# EMG_connectors_and_filters_CH_1_4.net
KiCad netlist of a schematic drawn in Altium Designer
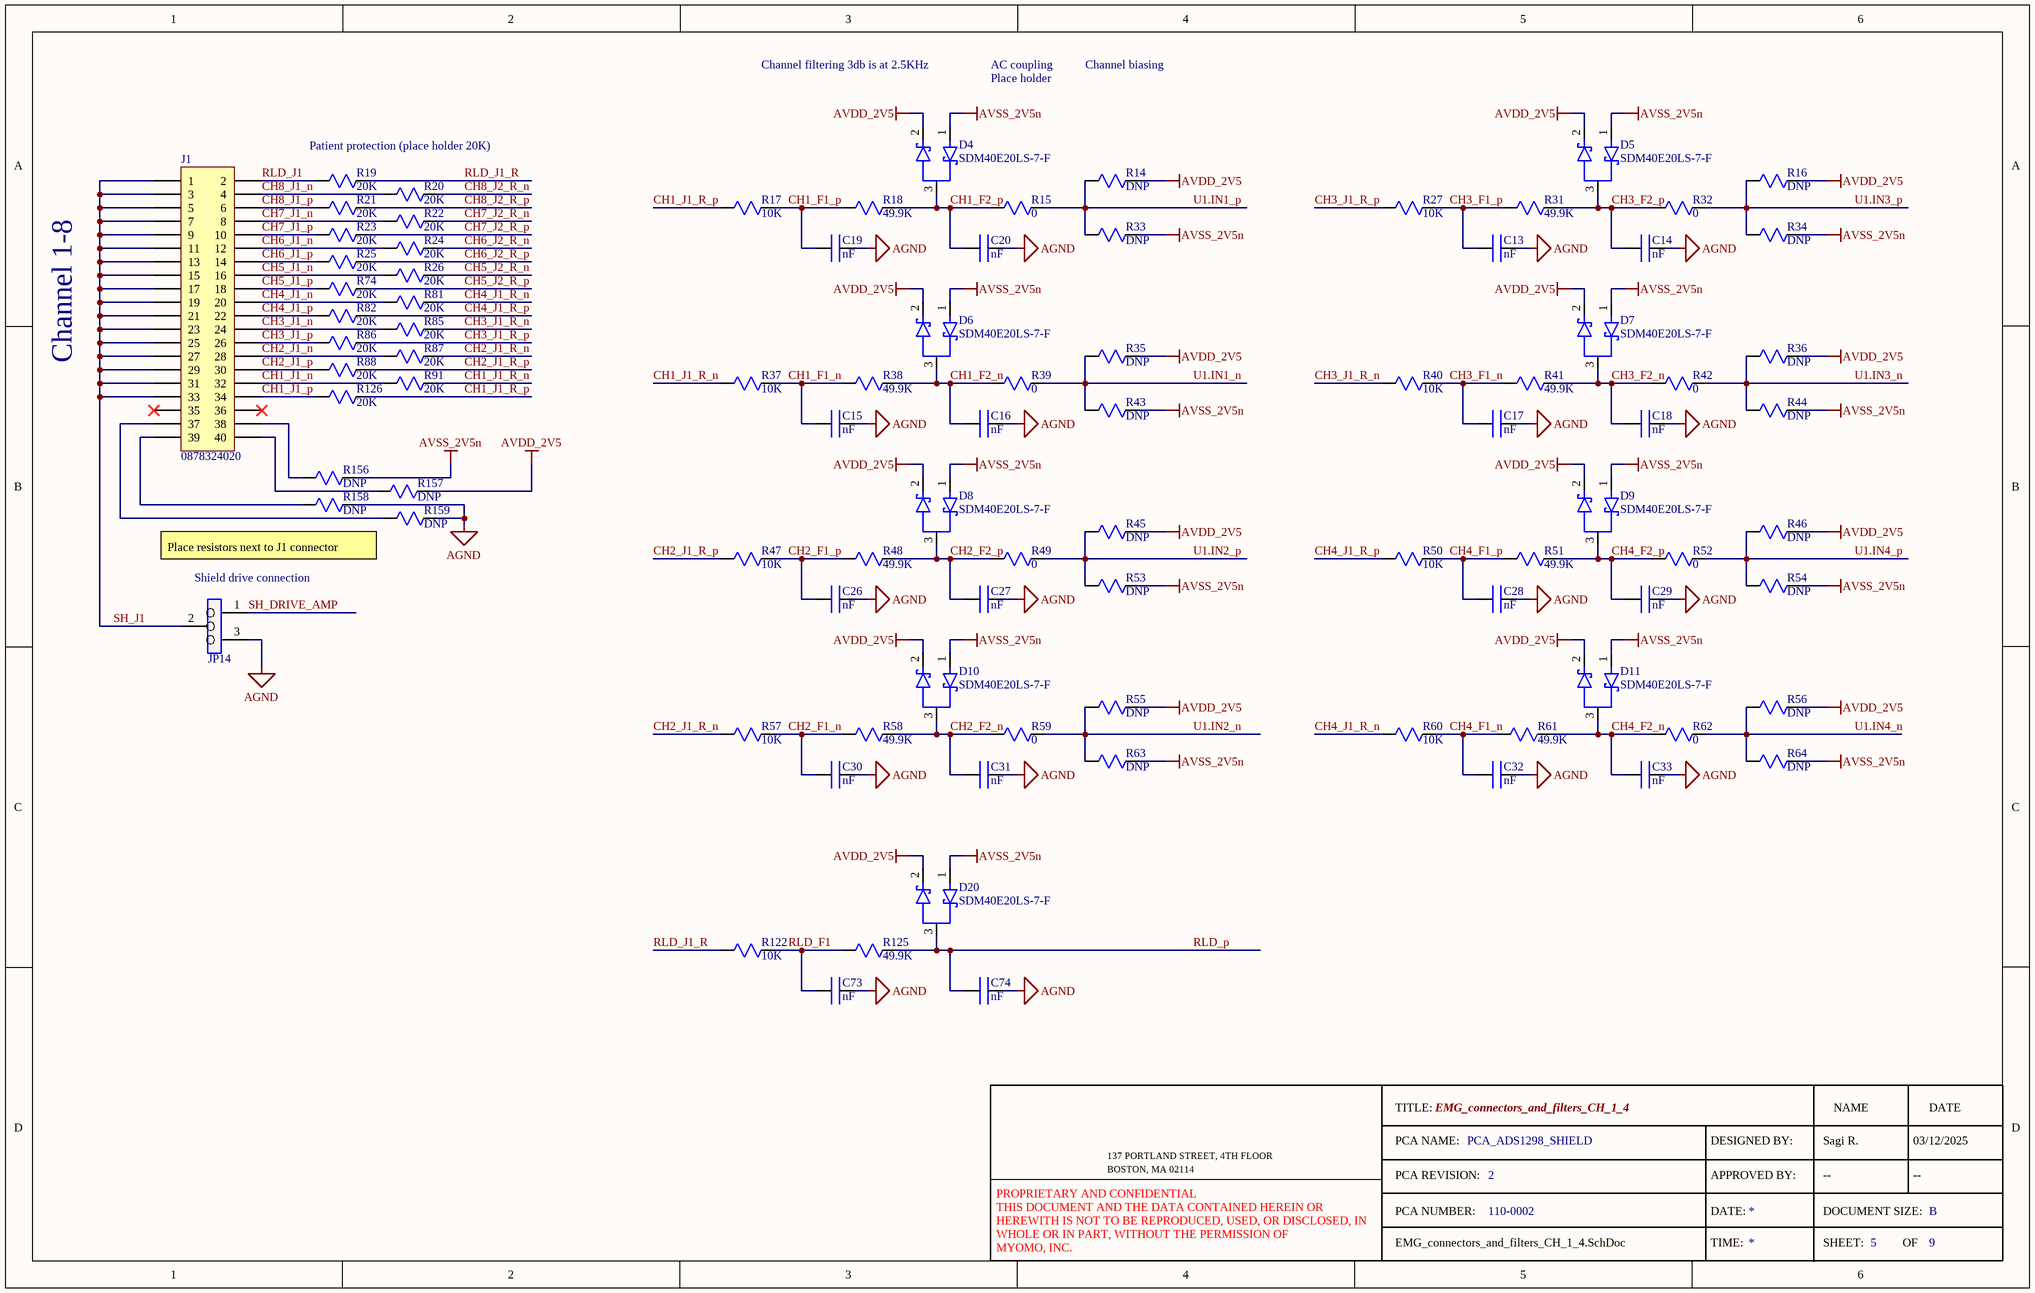
[diagram p0: EMG_connectors_and_filters_CH_1_4.SchDoc]

(export (version "E")
  (design (tool "Eeschema 10.0.6"))
  (components
    (comp (ref "C13")
      (value "nF")
      (footprint "0402")
      (description "CAP CER 1000PF 50V X7R 0402")
      (fields (field (name "MFG") "Samsung"))
      (libsource (lib "Myomo_SCH_Library") (part "C_0402_CER_1nF_50V_X7R"))
    )
    (comp (ref "C14")
      (value "nF")
      (footprint "0402")
      (description "CAP CER 1000PF 50V X7R 0402")
      (fields (field (name "MFG") "Samsung"))
      (libsource (lib "Myomo_SCH_Library") (part "C_0402_CER_1nF_50V_X7R"))
    )
    (comp (ref "C15")
      (value "nF")
      (footprint "0402")
      (description "CAP CER 1000PF 50V X7R 0402")
      (fields (field (name "MFG") "Samsung"))
      (libsource (lib "Myomo_SCH_Library") (part "C_0402_CER_1nF_50V_X7R"))
    )
    (comp (ref "C16")
      (value "nF")
      (footprint "0402")
      (description "CAP CER 1000PF 50V X7R 0402")
      (fields (field (name "MFG") "Samsung"))
      (libsource (lib "Myomo_SCH_Library") (part "C_0402_CER_1nF_50V_X7R"))
    )
    (comp (ref "C17")
      (value "nF")
      (footprint "0402")
      (description "CAP CER 1000PF 50V X7R 0402")
      (fields (field (name "MFG") "Samsung"))
      (libsource (lib "Myomo_SCH_Library") (part "C_0402_CER_1nF_50V_X7R"))
    )
    (comp (ref "C18")
      (value "nF")
      (footprint "0402")
      (description "CAP CER 1000PF 50V X7R 0402")
      (fields (field (name "MFG") "Samsung"))
      (libsource (lib "Myomo_SCH_Library") (part "C_0402_CER_1nF_50V_X7R"))
    )
    (comp (ref "C19")
      (value "nF")
      (footprint "0402")
      (description "CAP CER 1000PF 50V X7R 0402")
      (fields (field (name "MFG") "Samsung"))
      (libsource (lib "Myomo_SCH_Library") (part "C_0402_CER_1nF_50V_X7R"))
    )
    (comp (ref "C20")
      (value "nF")
      (footprint "0402")
      (description "CAP CER 1000PF 50V X7R 0402")
      (fields (field (name "MFG") "Samsung"))
      (libsource (lib "Myomo_SCH_Library") (part "C_0402_CER_1nF_50V_X7R"))
    )
    (comp (ref "C26")
      (value "nF")
      (footprint "0402")
      (description "CAP CER 1000PF 50V X7R 0402")
      (fields (field (name "MFG") "Samsung"))
      (libsource (lib "Myomo_SCH_Library") (part "C_0402_CER_1nF_50V_X7R"))
    )
    (comp (ref "C27")
      (value "nF")
      (footprint "0402")
      (description "CAP CER 1000PF 50V X7R 0402")
      (fields (field (name "MFG") "Samsung"))
      (libsource (lib "Myomo_SCH_Library") (part "C_0402_CER_1nF_50V_X7R"))
    )
    (comp (ref "C28")
      (value "nF")
      (footprint "0402")
      (description "CAP CER 1000PF 50V X7R 0402")
      (fields (field (name "MFG") "Samsung"))
      (libsource (lib "Myomo_SCH_Library") (part "C_0402_CER_1nF_50V_X7R"))
    )
    (comp (ref "C29")
      (value "nF")
      (footprint "0402")
      (description "CAP CER 1000PF 50V X7R 0402")
      (fields (field (name "MFG") "Samsung"))
      (libsource (lib "Myomo_SCH_Library") (part "C_0402_CER_1nF_50V_X7R"))
    )
    (comp (ref "C30")
      (value "nF")
      (footprint "0402")
      (description "CAP CER 1000PF 50V X7R 0402")
      (fields (field (name "MFG") "Samsung"))
      (libsource (lib "Myomo_SCH_Library") (part "C_0402_CER_1nF_50V_X7R"))
    )
    (comp (ref "C31")
      (value "nF")
      (footprint "0402")
      (description "CAP CER 1000PF 50V X7R 0402")
      (fields (field (name "MFG") "Samsung"))
      (libsource (lib "Myomo_SCH_Library") (part "C_0402_CER_1nF_50V_X7R"))
    )
    (comp (ref "C32")
      (value "nF")
      (footprint "0402")
      (description "CAP CER 1000PF 50V X7R 0402")
      (fields (field (name "MFG") "Samsung"))
      (libsource (lib "Myomo_SCH_Library") (part "C_0402_CER_1nF_50V_X7R"))
    )
    (comp (ref "C33")
      (value "nF")
      (footprint "0402")
      (description "CAP CER 1000PF 50V X7R 0402")
      (fields (field (name "MFG") "Samsung"))
      (libsource (lib "Myomo_SCH_Library") (part "C_0402_CER_1nF_50V_X7R"))
    )
    (comp (ref "C73")
      (value "nF")
      (footprint "0402")
      (description "CAP CER 1000PF 50V X7R 0402")
      (fields (field (name "MFG") "Samsung"))
      (libsource (lib "Myomo_SCH_Library") (part "C_0402_CER_1nF_50V_X7R"))
    )
    (comp (ref "C74")
      (value "nF")
      (footprint "0402")
      (description "CAP CER 1000PF 50V X7R 0402")
      (fields (field (name "MFG") "Samsung"))
      (libsource (lib "Myomo_SCH_Library") (part "C_0402_CER_1nF_50V_X7R"))
    )
    (comp (ref "D4")
      (value "SDM40E20LS-7-F")
      (footprint "D_SCHOTT_0.31mV_400mA")
      (description "DIODE ARR SCHOTT 20V 400MA SOT23")
      (fields (field (name "MFG") "Diodes Incorporated"))
      (libsource (lib "Myomo_SCH_Library") (part "D_SCHOTT_0.31mV_400mA"))
    )
    (comp (ref "D5")
      (value "SDM40E20LS-7-F")
      (footprint "D_SCHOTT_0.31mV_400mA")
      (description "DIODE ARR SCHOTT 20V 400MA SOT23")
      (fields (field (name "MFG") "Diodes Incorporated"))
      (libsource (lib "Myomo_SCH_Library") (part "D_SCHOTT_0.31mV_400mA"))
    )
    (comp (ref "D6")
      (value "SDM40E20LS-7-F")
      (footprint "D_SCHOTT_0.31mV_400mA")
      (description "DIODE ARR SCHOTT 20V 400MA SOT23")
      (fields (field (name "MFG") "Diodes Incorporated"))
      (libsource (lib "Myomo_SCH_Library") (part "D_SCHOTT_0.31mV_400mA"))
    )
    (comp (ref "D7")
      (value "SDM40E20LS-7-F")
      (footprint "D_SCHOTT_0.31mV_400mA")
      (description "DIODE ARR SCHOTT 20V 400MA SOT23")
      (fields (field (name "MFG") "Diodes Incorporated"))
      (libsource (lib "Myomo_SCH_Library") (part "D_SCHOTT_0.31mV_400mA"))
    )
    (comp (ref "D8")
      (value "SDM40E20LS-7-F")
      (footprint "D_SCHOTT_0.31mV_400mA")
      (description "DIODE ARR SCHOTT 20V 400MA SOT23")
      (fields (field (name "MFG") "Diodes Incorporated"))
      (libsource (lib "Myomo_SCH_Library") (part "D_SCHOTT_0.31mV_400mA"))
    )
    (comp (ref "D9")
      (value "SDM40E20LS-7-F")
      (footprint "D_SCHOTT_0.31mV_400mA")
      (description "DIODE ARR SCHOTT 20V 400MA SOT23")
      (fields (field (name "MFG") "Diodes Incorporated"))
      (libsource (lib "Myomo_SCH_Library") (part "D_SCHOTT_0.31mV_400mA"))
    )
    (comp (ref "D10")
      (value "SDM40E20LS-7-F")
      (footprint "D_SCHOTT_0.31mV_400mA")
      (description "DIODE ARR SCHOTT 20V 400MA SOT23")
      (fields (field (name "MFG") "Diodes Incorporated"))
      (libsource (lib "Myomo_SCH_Library") (part "D_SCHOTT_0.31mV_400mA"))
    )
    (comp (ref "D11")
      (value "SDM40E20LS-7-F")
      (footprint "D_SCHOTT_0.31mV_400mA")
      (description "DIODE ARR SCHOTT 20V 400MA SOT23")
      (fields (field (name "MFG") "Diodes Incorporated"))
      (libsource (lib "Myomo_SCH_Library") (part "D_SCHOTT_0.31mV_400mA"))
    )
    (comp (ref "D20")
      (value "SDM40E20LS-7-F")
      (footprint "D_SCHOTT_0.31mV_400mA")
      (description "DIODE ARR SCHOTT 20V 400MA SOT23")
      (fields (field (name "MFG") "Diodes Incorporated"))
      (libsource (lib "Myomo_SCH_Library") (part "D_SCHOTT_0.31mV_400mA"))
    )
    (comp (ref "J1")
      (value "0878324020")
      (footprint "J_MOLEX_0878324020")
      (description "CONN HEADER SMD 40POS 2MM PITCH")
      (fields (field (name "MFG") "Molex"))
      (libsource (lib "Myomo_SCH_Library") (part "J_MOLEX_0878324020"))
    )
    (comp (ref "JP14")
      (value "JP_1x3_TSW-103-07-F-S")
      (footprint "JP_1x3_TSW-103-07-F-S")
      (description "CONN HEADER VERT 2POS 2.54MM")
      (fields (field (name "MFG") "SAMTEC"))
      (libsource (lib "Myomo_SCH_Library") (part "JP_1x3_TSW-103-07-F-S"))
    )
    (comp (ref "R14")
      (value "DNP")
      (footprint "0402")
      (description "RES 0402 DNP")
      (libsource (lib "Myomo_SCH_Library") (part "R_0402_DNP"))
    )
    (comp (ref "R15")
      (value "0")
      (footprint "0402")
      (description "RES 0 OHM JUMPER 1/10W 0402")
      (fields (field (name "MFG") "YAGEO"))
      (libsource (lib "Myomo_SCH_Library") (part "R_0402_0"))
    )
    (comp (ref "R16")
      (value "DNP")
      (footprint "0402")
      (description "RES 0402 DNP")
      (libsource (lib "Myomo_SCH_Library") (part "R_0402_DNP"))
    )
    (comp (ref "R17")
      (value "10K")
      (footprint "0402")
      (description "RES SMD 10K OHM 1% 1/10W 0402")
      (fields (field (name "MFG") "Panasonic"))
      (libsource (lib "Myomo_SCH_Library") (part "R_0402_10K_1%_1/10W"))
    )
    (comp (ref "R18")
      (value "49.9K")
      (footprint "0402")
      (description "RES SMD 49.9 OHM 1% 1/10W 0402")
      (fields (field (name "MFG") "Panasonic"))
      (libsource (lib "Myomo_SCH_Library") (part "R_0402_49.9K_1%_1/10W"))
    )
    (comp (ref "R19")
      (value "20K")
      (footprint "0603")
      (description "RES 20K OHM 1% 1/10W 0603")
      (fields (field (name "MFG") "YAGEO"))
      (libsource (lib "Myomo_SCH_Library") (part "R_0603_20K_1%_1/10W"))
    )
    (comp (ref "R20")
      (value "20K")
      (footprint "0603")
      (description "RES 20K OHM 1% 1/10W 0603")
      (fields (field (name "MFG") "YAGEO"))
      (libsource (lib "Myomo_SCH_Library") (part "R_0603_20K_1%_1/10W"))
    )
    (comp (ref "R21")
      (value "20K")
      (footprint "0603")
      (description "RES 20K OHM 1% 1/10W 0603")
      (fields (field (name "MFG") "YAGEO"))
      (libsource (lib "Myomo_SCH_Library") (part "R_0603_20K_1%_1/10W"))
    )
    (comp (ref "R22")
      (value "20K")
      (footprint "0603")
      (description "RES 20K OHM 1% 1/10W 0603")
      (fields (field (name "MFG") "YAGEO"))
      (libsource (lib "Myomo_SCH_Library") (part "R_0603_20K_1%_1/10W"))
    )
    (comp (ref "R23")
      (value "20K")
      (footprint "0603")
      (description "RES 20K OHM 1% 1/10W 0603")
      (fields (field (name "MFG") "YAGEO"))
      (libsource (lib "Myomo_SCH_Library") (part "R_0603_20K_1%_1/10W"))
    )
    (comp (ref "R24")
      (value "20K")
      (footprint "0603")
      (description "RES 20K OHM 1% 1/10W 0603")
      (fields (field (name "MFG") "YAGEO"))
      (libsource (lib "Myomo_SCH_Library") (part "R_0603_20K_1%_1/10W"))
    )
    (comp (ref "R25")
      (value "20K")
      (footprint "0603")
      (description "RES 20K OHM 1% 1/10W 0603")
      (fields (field (name "MFG") "YAGEO"))
      (libsource (lib "Myomo_SCH_Library") (part "R_0603_20K_1%_1/10W"))
    )
    (comp (ref "R26")
      (value "20K")
      (footprint "0603")
      (description "RES 20K OHM 1% 1/10W 0603")
      (fields (field (name "MFG") "YAGEO"))
      (libsource (lib "Myomo_SCH_Library") (part "R_0603_20K_1%_1/10W"))
    )
    (comp (ref "R27")
      (value "10K")
      (footprint "0402")
      (description "RES SMD 10K OHM 1% 1/10W 0402")
      (fields (field (name "MFG") "Panasonic"))
      (libsource (lib "Myomo_SCH_Library") (part "R_0402_10K_1%_1/10W"))
    )
    (comp (ref "R31")
      (value "49.9K")
      (footprint "0402")
      (description "RES SMD 49.9 OHM 1% 1/10W 0402")
      (fields (field (name "MFG") "Panasonic"))
      (libsource (lib "Myomo_SCH_Library") (part "R_0402_49.9K_1%_1/10W"))
    )
    (comp (ref "R32")
      (value "0")
      (footprint "0402")
      (description "RES 0 OHM JUMPER 1/10W 0402")
      (fields (field (name "MFG") "YAGEO"))
      (libsource (lib "Myomo_SCH_Library") (part "R_0402_0"))
    )
    (comp (ref "R33")
      (value "DNP")
      (footprint "0402")
      (description "RES 0402 DNP")
      (libsource (lib "Myomo_SCH_Library") (part "R_0402_DNP"))
    )
    (comp (ref "R34")
      (value "DNP")
      (footprint "0402")
      (description "RES 0402 DNP")
      (libsource (lib "Myomo_SCH_Library") (part "R_0402_DNP"))
    )
    (comp (ref "R35")
      (value "DNP")
      (footprint "0402")
      (description "RES 0402 DNP")
      (libsource (lib "Myomo_SCH_Library") (part "R_0402_DNP"))
    )
    (comp (ref "R36")
      (value "DNP")
      (footprint "0402")
      (description "RES 0402 DNP")
      (libsource (lib "Myomo_SCH_Library") (part "R_0402_DNP"))
    )
    (comp (ref "R37")
      (value "10K")
      (footprint "0402")
      (description "RES SMD 10K OHM 1% 1/10W 0402")
      (fields (field (name "MFG") "Panasonic"))
      (libsource (lib "Myomo_SCH_Library") (part "R_0402_10K_1%_1/10W"))
    )
    (comp (ref "R38")
      (value "49.9K")
      (footprint "0402")
      (description "RES SMD 49.9 OHM 1% 1/10W 0402")
      (fields (field (name "MFG") "Panasonic"))
      (libsource (lib "Myomo_SCH_Library") (part "R_0402_49.9K_1%_1/10W"))
    )
    (comp (ref "R39")
      (value "0")
      (footprint "0402")
      (description "RES 0 OHM JUMPER 1/10W 0402")
      (fields (field (name "MFG") "YAGEO"))
      (libsource (lib "Myomo_SCH_Library") (part "R_0402_0"))
    )
    (comp (ref "R40")
      (value "10K")
      (footprint "0402")
      (description "RES SMD 10K OHM 1% 1/10W 0402")
      (fields (field (name "MFG") "Panasonic"))
      (libsource (lib "Myomo_SCH_Library") (part "R_0402_10K_1%_1/10W"))
    )
    (comp (ref "R41")
      (value "49.9K")
      (footprint "0402")
      (description "RES SMD 49.9 OHM 1% 1/10W 0402")
      (fields (field (name "MFG") "Panasonic"))
      (libsource (lib "Myomo_SCH_Library") (part "R_0402_49.9K_1%_1/10W"))
    )
    (comp (ref "R42")
      (value "0")
      (footprint "0402")
      (description "RES 0 OHM JUMPER 1/10W 0402")
      (fields (field (name "MFG") "YAGEO"))
      (libsource (lib "Myomo_SCH_Library") (part "R_0402_0"))
    )
    (comp (ref "R43")
      (value "DNP")
      (footprint "0402")
      (description "RES 0402 DNP")
      (libsource (lib "Myomo_SCH_Library") (part "R_0402_DNP"))
    )
    (comp (ref "R44")
      (value "DNP")
      (footprint "0402")
      (description "RES 0402 DNP")
      (libsource (lib "Myomo_SCH_Library") (part "R_0402_DNP"))
    )
    (comp (ref "R45")
      (value "DNP")
      (footprint "0402")
      (description "RES 0402 DNP")
      (libsource (lib "Myomo_SCH_Library") (part "R_0402_DNP"))
    )
    (comp (ref "R46")
      (value "DNP")
      (footprint "0402")
      (description "RES 0402 DNP")
      (libsource (lib "Myomo_SCH_Library") (part "R_0402_DNP"))
    )
    (comp (ref "R47")
      (value "10K")
      (footprint "0402")
      (description "RES SMD 10K OHM 1% 1/10W 0402")
      (fields (field (name "MFG") "Panasonic"))
      (libsource (lib "Myomo_SCH_Library") (part "R_0402_10K_1%_1/10W"))
    )
    (comp (ref "R48")
      (value "49.9K")
      (footprint "0402")
      (description "RES SMD 49.9 OHM 1% 1/10W 0402")
      (fields (field (name "MFG") "Panasonic"))
      (libsource (lib "Myomo_SCH_Library") (part "R_0402_49.9K_1%_1/10W"))
    )
    (comp (ref "R49")
      (value "0")
      (footprint "0402")
      (description "RES 0 OHM JUMPER 1/10W 0402")
      (fields (field (name "MFG") "YAGEO"))
      (libsource (lib "Myomo_SCH_Library") (part "R_0402_0"))
    )
    (comp (ref "R50")
      (value "10K")
      (footprint "0402")
      (description "RES SMD 10K OHM 1% 1/10W 0402")
      (fields (field (name "MFG") "Panasonic"))
      (libsource (lib "Myomo_SCH_Library") (part "R_0402_10K_1%_1/10W"))
    )
    (comp (ref "R51")
      (value "49.9K")
      (footprint "0402")
      (description "RES SMD 49.9 OHM 1% 1/10W 0402")
      (fields (field (name "MFG") "Panasonic"))
      (libsource (lib "Myomo_SCH_Library") (part "R_0402_49.9K_1%_1/10W"))
    )
    (comp (ref "R52")
      (value "0")
      (footprint "0402")
      (description "RES 0 OHM JUMPER 1/10W 0402")
      (fields (field (name "MFG") "YAGEO"))
      (libsource (lib "Myomo_SCH_Library") (part "R_0402_0"))
    )
    (comp (ref "R53")
      (value "DNP")
      (footprint "0402")
      (description "RES 0402 DNP")
      (libsource (lib "Myomo_SCH_Library") (part "R_0402_DNP"))
    )
    (comp (ref "R54")
      (value "DNP")
      (footprint "0402")
      (description "RES 0402 DNP")
      (libsource (lib "Myomo_SCH_Library") (part "R_0402_DNP"))
    )
    (comp (ref "R55")
      (value "DNP")
      (footprint "0402")
      (description "RES 0402 DNP")
      (libsource (lib "Myomo_SCH_Library") (part "R_0402_DNP"))
    )
    (comp (ref "R56")
      (value "DNP")
      (footprint "0402")
      (description "RES 0402 DNP")
      (libsource (lib "Myomo_SCH_Library") (part "R_0402_DNP"))
    )
    (comp (ref "R57")
      (value "10K")
      (footprint "0402")
      (description "RES SMD 10K OHM 1% 1/10W 0402")
      (fields (field (name "MFG") "Panasonic"))
      (libsource (lib "Myomo_SCH_Library") (part "R_0402_10K_1%_1/10W"))
    )
    (comp (ref "R58")
      (value "49.9K")
      (footprint "0402")
      (description "RES SMD 49.9 OHM 1% 1/10W 0402")
      (fields (field (name "MFG") "Panasonic"))
      (libsource (lib "Myomo_SCH_Library") (part "R_0402_49.9K_1%_1/10W"))
    )
    (comp (ref "R59")
      (value "0")
      (footprint "0402")
      (description "RES 0 OHM JUMPER 1/10W 0402")
      (fields (field (name "MFG") "YAGEO"))
      (libsource (lib "Myomo_SCH_Library") (part "R_0402_0"))
    )
    (comp (ref "R60")
      (value "10K")
      (footprint "0402")
      (description "RES SMD 10K OHM 1% 1/10W 0402")
      (fields (field (name "MFG") "Panasonic"))
      (libsource (lib "Myomo_SCH_Library") (part "R_0402_10K_1%_1/10W"))
    )
    (comp (ref "R61")
      (value "49.9K")
      (footprint "0402")
      (description "RES SMD 49.9 OHM 1% 1/10W 0402")
      (fields (field (name "MFG") "Panasonic"))
      (libsource (lib "Myomo_SCH_Library") (part "R_0402_49.9K_1%_1/10W"))
    )
    (comp (ref "R62")
      (value "0")
      (footprint "0402")
      (description "RES 0 OHM JUMPER 1/10W 0402")
      (fields (field (name "MFG") "YAGEO"))
      (libsource (lib "Myomo_SCH_Library") (part "R_0402_0"))
    )
    (comp (ref "R63")
      (value "DNP")
      (footprint "0402")
      (description "RES 0402 DNP")
      (libsource (lib "Myomo_SCH_Library") (part "R_0402_DNP"))
    )
    (comp (ref "R64")
      (value "DNP")
      (footprint "0402")
      (description "RES 0402 DNP")
      (libsource (lib "Myomo_SCH_Library") (part "R_0402_DNP"))
    )
    (comp (ref "R74")
      (value "20K")
      (footprint "0603")
      (description "RES 20K OHM 1% 1/10W 0603")
      (fields (field (name "MFG") "YAGEO"))
      (libsource (lib "Myomo_SCH_Library") (part "R_0603_20K_1%_1/10W"))
    )
    (comp (ref "R81")
      (value "20K")
      (footprint "0603")
      (description "RES 20K OHM 1% 1/10W 0603")
      (fields (field (name "MFG") "YAGEO"))
      (libsource (lib "Myomo_SCH_Library") (part "R_0603_20K_1%_1/10W"))
    )
    (comp (ref "R82")
      (value "20K")
      (footprint "0603")
      (description "RES 20K OHM 1% 1/10W 0603")
      (fields (field (name "MFG") "YAGEO"))
      (libsource (lib "Myomo_SCH_Library") (part "R_0603_20K_1%_1/10W"))
    )
    (comp (ref "R85")
      (value "20K")
      (footprint "0603")
      (description "RES 20K OHM 1% 1/10W 0603")
      (fields (field (name "MFG") "YAGEO"))
      (libsource (lib "Myomo_SCH_Library") (part "R_0603_20K_1%_1/10W"))
    )
    (comp (ref "R86")
      (value "20K")
      (footprint "0603")
      (description "RES 20K OHM 1% 1/10W 0603")
      (fields (field (name "MFG") "YAGEO"))
      (libsource (lib "Myomo_SCH_Library") (part "R_0603_20K_1%_1/10W"))
    )
    (comp (ref "R87")
      (value "20K")
      (footprint "0603")
      (description "RES 20K OHM 1% 1/10W 0603")
      (fields (field (name "MFG") "YAGEO"))
      (libsource (lib "Myomo_SCH_Library") (part "R_0603_20K_1%_1/10W"))
    )
    (comp (ref "R88")
      (value "20K")
      (footprint "0603")
      (description "RES 20K OHM 1% 1/10W 0603")
      (fields (field (name "MFG") "YAGEO"))
      (libsource (lib "Myomo_SCH_Library") (part "R_0603_20K_1%_1/10W"))
    )
    (comp (ref "R91")
      (value "20K")
      (footprint "0603")
      (description "RES 20K OHM 1% 1/10W 0603")
      (fields (field (name "MFG") "YAGEO"))
      (libsource (lib "Myomo_SCH_Library") (part "R_0603_20K_1%_1/10W"))
    )
    (comp (ref "R122")
      (value "10K")
      (footprint "0402")
      (description "RES SMD 10K OHM 1% 1/10W 0402")
      (fields (field (name "MFG") "Panasonic"))
      (libsource (lib "Myomo_SCH_Library") (part "R_0402_10K_1%_1/10W"))
    )
    (comp (ref "R125")
      (value "49.9K")
      (footprint "0402")
      (description "RES SMD 49.9 OHM 1% 1/10W 0402")
      (fields (field (name "MFG") "Panasonic"))
      (libsource (lib "Myomo_SCH_Library") (part "R_0402_49.9K_1%_1/10W"))
    )
    (comp (ref "R126")
      (value "20K")
      (footprint "0603")
      (description "RES 20K OHM 1% 1/10W 0603")
      (fields (field (name "MFG") "YAGEO"))
      (libsource (lib "Myomo_SCH_Library") (part "R_0603_20K_1%_1/10W"))
    )
    (comp (ref "R156")
      (value "DNP")
      (footprint "0603")
      (description "RES 0603 DNP")
      (libsource (lib "Myomo_SCH_Library") (part "R_0603_DNP"))
    )
    (comp (ref "R157")
      (value "DNP")
      (footprint "0603")
      (description "RES 0603 DNP")
      (libsource (lib "Myomo_SCH_Library") (part "R_0603_DNP"))
    )
    (comp (ref "R158")
      (value "DNP")
      (footprint "0603")
      (description "RES 0603 DNP")
      (libsource (lib "Myomo_SCH_Library") (part "R_0603_DNP"))
    )
    (comp (ref "R159")
      (value "DNP")
      (footprint "0603")
      (description "RES 0603 DNP")
      (libsource (lib "Myomo_SCH_Library") (part "R_0603_DNP"))
    )
  )
  (nets
    (net (code "1") (name "/CH1_F1_n") (class "Default")
      (node (ref "C15") (pin "1") (pinfunction "1_1") (pintype "passive"))
      (node (ref "R37") (pin "2") (pinfunction "2_2") (pintype "passive"))
      (node (ref "R38") (pin "1") (pinfunction "1_1") (pintype "passive"))
    )
    (net (code "2") (name "/CH1_F1_p") (class "Default")
      (node (ref "C19") (pin "1") (pinfunction "1_1") (pintype "passive"))
      (node (ref "R17") (pin "2") (pinfunction "2_2") (pintype "passive"))
      (node (ref "R18") (pin "1") (pinfunction "1_1") (pintype "passive"))
    )
    (net (code "3") (name "/CH1_F2_n") (class "Default")
      (node (ref "C16") (pin "1") (pinfunction "1_1") (pintype "passive"))
      (node (ref "D6") (pin "3") (pinfunction "K_3") (pintype "passive"))
      (node (ref "R38") (pin "2") (pinfunction "2_2") (pintype "passive"))
      (node (ref "R39") (pin "1") (pinfunction "1_1") (pintype "passive"))
    )
    (net (code "4") (name "/CH1_F2_p") (class "Default")
      (node (ref "C20") (pin "1") (pinfunction "1_1") (pintype "passive"))
      (node (ref "D4") (pin "3") (pinfunction "K_3") (pintype "passive"))
      (node (ref "R15") (pin "1") (pinfunction "1_1") (pintype "passive"))
      (node (ref "R18") (pin "2") (pinfunction "2_2") (pintype "passive"))
    )
    (net (code "5") (name "/CH1_J1_R_n") (class "Default")
      (node (ref "R37") (pin "1") (pinfunction "1_1") (pintype "passive"))
      (node (ref "R91") (pin "2") (pinfunction "2_2") (pintype "passive"))
    )
    (net (code "6") (name "/CH1_J1_R_p") (class "Default")
      (node (ref "R126") (pin "2") (pinfunction "2_2") (pintype "passive"))
      (node (ref "R17") (pin "1") (pinfunction "1_1") (pintype "passive"))
    )
    (net (code "7") (name "/CH1_J1_n") (class "Default")
      (node (ref "J1") (pin "32") (pinfunction "32_32") (pintype "passive"))
      (node (ref "R91") (pin "1") (pinfunction "1_1") (pintype "passive"))
    )
    (net (code "8") (name "/CH1_J1_p") (class "Default")
      (node (ref "J1") (pin "34") (pinfunction "34_34") (pintype "passive"))
      (node (ref "R126") (pin "1") (pinfunction "1_1") (pintype "passive"))
    )
    (net (code "9") (name "/CH2_F1_n") (class "Default")
      (node (ref "C30") (pin "1") (pinfunction "1_1") (pintype "passive"))
      (node (ref "R57") (pin "2") (pinfunction "2_2") (pintype "passive"))
      (node (ref "R58") (pin "1") (pinfunction "1_1") (pintype "passive"))
    )
    (net (code "10") (name "/CH2_F1_p") (class "Default")
      (node (ref "C26") (pin "1") (pinfunction "1_1") (pintype "passive"))
      (node (ref "R47") (pin "2") (pinfunction "2_2") (pintype "passive"))
      (node (ref "R48") (pin "1") (pinfunction "1_1") (pintype "passive"))
    )
    (net (code "11") (name "/CH2_F2_n") (class "Default")
      (node (ref "C31") (pin "1") (pinfunction "1_1") (pintype "passive"))
      (node (ref "D10") (pin "3") (pinfunction "K_3") (pintype "passive"))
      (node (ref "R58") (pin "2") (pinfunction "2_2") (pintype "passive"))
      (node (ref "R59") (pin "1") (pinfunction "1_1") (pintype "passive"))
    )
    (net (code "12") (name "/CH2_F2_p") (class "Default")
      (node (ref "C27") (pin "1") (pinfunction "1_1") (pintype "passive"))
      (node (ref "D8") (pin "3") (pinfunction "K_3") (pintype "passive"))
      (node (ref "R48") (pin "2") (pinfunction "2_2") (pintype "passive"))
      (node (ref "R49") (pin "1") (pinfunction "1_1") (pintype "passive"))
    )
    (net (code "13") (name "/CH2_J1_R_n") (class "Default")
      (node (ref "R57") (pin "1") (pinfunction "1_1") (pintype "passive"))
      (node (ref "R87") (pin "2") (pinfunction "2_2") (pintype "passive"))
    )
    (net (code "14") (name "/CH2_J1_R_p") (class "Default")
      (node (ref "R47") (pin "1") (pinfunction "1_1") (pintype "passive"))
      (node (ref "R88") (pin "2") (pinfunction "2_2") (pintype "passive"))
    )
    (net (code "15") (name "/CH2_J1_n") (class "Default")
      (node (ref "J1") (pin "28") (pinfunction "28_28") (pintype "passive"))
      (node (ref "R87") (pin "1") (pinfunction "1_1") (pintype "passive"))
    )
    (net (code "16") (name "/CH2_J1_p") (class "Default")
      (node (ref "J1") (pin "30") (pinfunction "30_30") (pintype "passive"))
      (node (ref "R88") (pin "1") (pinfunction "1_1") (pintype "passive"))
    )
    (net (code "17") (name "/CH3_F1_n") (class "Default")
      (node (ref "C17") (pin "1") (pinfunction "1_1") (pintype "passive"))
      (node (ref "R40") (pin "2") (pinfunction "2_2") (pintype "passive"))
      (node (ref "R41") (pin "1") (pinfunction "1_1") (pintype "passive"))
    )
    (net (code "18") (name "/CH3_F1_p") (class "Default")
      (node (ref "C13") (pin "1") (pinfunction "1_1") (pintype "passive"))
      (node (ref "R27") (pin "2") (pinfunction "2_2") (pintype "passive"))
      (node (ref "R31") (pin "1") (pinfunction "1_1") (pintype "passive"))
    )
    (net (code "19") (name "/CH3_F2_n") (class "Default")
      (node (ref "C18") (pin "1") (pinfunction "1_1") (pintype "passive"))
      (node (ref "D7") (pin "3") (pinfunction "K_3") (pintype "passive"))
      (node (ref "R41") (pin "2") (pinfunction "2_2") (pintype "passive"))
      (node (ref "R42") (pin "1") (pinfunction "1_1") (pintype "passive"))
    )
    (net (code "20") (name "/CH3_F2_p") (class "Default")
      (node (ref "C14") (pin "1") (pinfunction "1_1") (pintype "passive"))
      (node (ref "D5") (pin "3") (pinfunction "K_3") (pintype "passive"))
      (node (ref "R31") (pin "2") (pinfunction "2_2") (pintype "passive"))
      (node (ref "R32") (pin "1") (pinfunction "1_1") (pintype "passive"))
    )
    (net (code "21") (name "/CH3_J1_R_n") (class "Default")
      (node (ref "R40") (pin "1") (pinfunction "1_1") (pintype "passive"))
      (node (ref "R85") (pin "2") (pinfunction "2_2") (pintype "passive"))
    )
    (net (code "22") (name "/CH3_J1_R_p") (class "Default")
      (node (ref "R27") (pin "1") (pinfunction "1_1") (pintype "passive"))
      (node (ref "R86") (pin "2") (pinfunction "2_2") (pintype "passive"))
    )
    (net (code "23") (name "/CH3_J1_n") (class "Default")
      (node (ref "J1") (pin "24") (pinfunction "24_24") (pintype "passive"))
      (node (ref "R85") (pin "1") (pinfunction "1_1") (pintype "passive"))
    )
    (net (code "24") (name "/CH3_J1_p") (class "Default")
      (node (ref "J1") (pin "26") (pinfunction "26_26") (pintype "passive"))
      (node (ref "R86") (pin "1") (pinfunction "1_1") (pintype "passive"))
    )
    (net (code "25") (name "/CH4_F1_n") (class "Default")
      (node (ref "C32") (pin "1") (pinfunction "1_1") (pintype "passive"))
      (node (ref "R60") (pin "2") (pinfunction "2_2") (pintype "passive"))
      (node (ref "R61") (pin "1") (pinfunction "1_1") (pintype "passive"))
    )
    (net (code "26") (name "/CH4_F1_p") (class "Default")
      (node (ref "C28") (pin "1") (pinfunction "1_1") (pintype "passive"))
      (node (ref "R50") (pin "2") (pinfunction "2_2") (pintype "passive"))
      (node (ref "R51") (pin "1") (pinfunction "1_1") (pintype "passive"))
    )
    (net (code "27") (name "/CH4_F2_n") (class "Default")
      (node (ref "C33") (pin "1") (pinfunction "1_1") (pintype "passive"))
      (node (ref "D11") (pin "3") (pinfunction "K_3") (pintype "passive"))
      (node (ref "R61") (pin "2") (pinfunction "2_2") (pintype "passive"))
      (node (ref "R62") (pin "1") (pinfunction "1_1") (pintype "passive"))
    )
    (net (code "28") (name "/CH4_F2_p") (class "Default")
      (node (ref "C29") (pin "1") (pinfunction "1_1") (pintype "passive"))
      (node (ref "D9") (pin "3") (pinfunction "K_3") (pintype "passive"))
      (node (ref "R51") (pin "2") (pinfunction "2_2") (pintype "passive"))
      (node (ref "R52") (pin "1") (pinfunction "1_1") (pintype "passive"))
    )
    (net (code "29") (name "/CH4_J1_R_n") (class "Default")
      (node (ref "R60") (pin "1") (pinfunction "1_1") (pintype "passive"))
      (node (ref "R81") (pin "2") (pinfunction "2_2") (pintype "passive"))
    )
    (net (code "30") (name "/CH4_J1_R_p") (class "Default")
      (node (ref "R50") (pin "1") (pinfunction "1_1") (pintype "passive"))
      (node (ref "R82") (pin "2") (pinfunction "2_2") (pintype "passive"))
    )
    (net (code "31") (name "/CH4_J1_n") (class "Default")
      (node (ref "J1") (pin "20") (pinfunction "20_20") (pintype "passive"))
      (node (ref "R81") (pin "1") (pinfunction "1_1") (pintype "passive"))
    )
    (net (code "32") (name "/CH4_J1_p") (class "Default")
      (node (ref "J1") (pin "22") (pinfunction "22_22") (pintype "passive"))
      (node (ref "R82") (pin "1") (pinfunction "1_1") (pintype "passive"))
    )
    (net (code "33") (name "/CH5_J1_n") (class "Default")
      (node (ref "J1") (pin "16") (pinfunction "16_16") (pintype "passive"))
      (node (ref "R26") (pin "1") (pinfunction "1_1") (pintype "passive"))
    )
    (net (code "34") (name "/CH5_J1_p") (class "Default")
      (node (ref "J1") (pin "18") (pinfunction "18_18") (pintype "passive"))
      (node (ref "R74") (pin "1") (pinfunction "1_1") (pintype "passive"))
    )
    (net (code "35") (name "/CH5_J2_R_n") (class "Default")
      (node (ref "R26") (pin "2") (pinfunction "2_2") (pintype "passive"))
    )
    (net (code "36") (name "/CH5_J2_R_p") (class "Default")
      (node (ref "R74") (pin "2") (pinfunction "2_2") (pintype "passive"))
    )
    (net (code "37") (name "/CH6_J1_n") (class "Default")
      (node (ref "J1") (pin "12") (pinfunction "12_12") (pintype "passive"))
      (node (ref "R24") (pin "1") (pinfunction "1_1") (pintype "passive"))
    )
    (net (code "38") (name "/CH6_J1_p") (class "Default")
      (node (ref "J1") (pin "14") (pinfunction "14_14") (pintype "passive"))
      (node (ref "R25") (pin "1") (pinfunction "1_1") (pintype "passive"))
    )
    (net (code "39") (name "/CH6_J2_R_n") (class "Default")
      (node (ref "R24") (pin "2") (pinfunction "2_2") (pintype "passive"))
    )
    (net (code "40") (name "/CH6_J2_R_p") (class "Default")
      (node (ref "R25") (pin "2") (pinfunction "2_2") (pintype "passive"))
    )
    (net (code "41") (name "/CH7_J1_n") (class "Default")
      (node (ref "J1") (pin "8") (pinfunction "8_8") (pintype "passive"))
      (node (ref "R22") (pin "1") (pinfunction "1_1") (pintype "passive"))
    )
    (net (code "42") (name "/CH7_J1_p") (class "Default")
      (node (ref "J1") (pin "10") (pinfunction "10_10") (pintype "passive"))
      (node (ref "R23") (pin "1") (pinfunction "1_1") (pintype "passive"))
    )
    (net (code "43") (name "/CH7_J2_R_n") (class "Default")
      (node (ref "R22") (pin "2") (pinfunction "2_2") (pintype "passive"))
    )
    (net (code "44") (name "/CH7_J2_R_p") (class "Default")
      (node (ref "R23") (pin "2") (pinfunction "2_2") (pintype "passive"))
    )
    (net (code "45") (name "/CH8_J1_n") (class "Default")
      (node (ref "J1") (pin "4") (pinfunction "4_4") (pintype "passive"))
      (node (ref "R20") (pin "1") (pinfunction "1_1") (pintype "passive"))
    )
    (net (code "46") (name "/CH8_J1_p") (class "Default")
      (node (ref "J1") (pin "6") (pinfunction "6_6") (pintype "passive"))
      (node (ref "R21") (pin "1") (pinfunction "1_1") (pintype "passive"))
    )
    (net (code "47") (name "/CH8_J2_R_n") (class "Default")
      (node (ref "R20") (pin "2") (pinfunction "2_2") (pintype "passive"))
    )
    (net (code "48") (name "/CH8_J2_R_p") (class "Default")
      (node (ref "R21") (pin "2") (pinfunction "2_2") (pintype "passive"))
    )
    (net (code "49") (name "/RLD_F1") (class "Default")
      (node (ref "C73") (pin "1") (pinfunction "1_1") (pintype "passive"))
      (node (ref "R122") (pin "2") (pinfunction "2_2") (pintype "passive"))
      (node (ref "R125") (pin "1") (pinfunction "1_1") (pintype "passive"))
    )
    (net (code "50") (name "/RLD_J1") (class "Default")
      (node (ref "J1") (pin "2") (pinfunction "2_2") (pintype "passive"))
      (node (ref "R19") (pin "1") (pinfunction "1_1") (pintype "passive"))
    )
    (net (code "51") (name "/RLD_J1_R") (class "Default")
      (node (ref "R122") (pin "1") (pinfunction "1_1") (pintype "passive"))
      (node (ref "R19") (pin "2") (pinfunction "2_2") (pintype "passive"))
    )
    (net (code "52") (name "/RLD_p") (class "Default")
      (node (ref "C74") (pin "1") (pinfunction "1_1") (pintype "passive"))
      (node (ref "D20") (pin "3") (pinfunction "K_3") (pintype "passive"))
      (node (ref "R125") (pin "2") (pinfunction "2_2") (pintype "passive"))
    )
    (net (code "53") (name "/SH_DRIVE_AMP") (class "Default")
      (node (ref "JP14") (pin "1") (pinfunction "1_1") (pintype "passive"))
    )
    (net (code "54") (name "/SH_J1") (class "Default")
      (node (ref "J1") (pin "1") (pinfunction "1_1") (pintype "passive"))
      (node (ref "J1") (pin "11") (pinfunction "11_11") (pintype "passive"))
      (node (ref "J1") (pin "13") (pinfunction "13_13") (pintype "passive"))
      (node (ref "J1") (pin "15") (pinfunction "15_15") (pintype "passive"))
      (node (ref "J1") (pin "17") (pinfunction "17_17") (pintype "passive"))
      (node (ref "J1") (pin "19") (pinfunction "19_19") (pintype "passive"))
      (node (ref "J1") (pin "21") (pinfunction "21_21") (pintype "passive"))
      (node (ref "J1") (pin "23") (pinfunction "23_23") (pintype "passive"))
      (node (ref "J1") (pin "25") (pinfunction "25_25") (pintype "passive"))
      (node (ref "J1") (pin "27") (pinfunction "27_27") (pintype "passive"))
      (node (ref "J1") (pin "29") (pinfunction "29_29") (pintype "passive"))
      (node (ref "J1") (pin "3") (pinfunction "3_3") (pintype "passive"))
      (node (ref "J1") (pin "31") (pinfunction "31_31") (pintype "passive"))
      (node (ref "J1") (pin "33") (pinfunction "33_33") (pintype "passive"))
      (node (ref "J1") (pin "5") (pinfunction "5_5") (pintype "passive"))
      (node (ref "J1") (pin "7") (pinfunction "7_7") (pintype "passive"))
      (node (ref "J1") (pin "9") (pinfunction "9_9") (pintype "passive"))
      (node (ref "JP14") (pin "2") (pinfunction "2_2") (pintype "passive"))
    )
    (net (code "55") (name "/U1.IN1_n") (class "Default")
      (node (ref "R35") (pin "1") (pinfunction "1_1") (pintype "passive"))
      (node (ref "R39") (pin "2") (pinfunction "2_2") (pintype "passive"))
      (node (ref "R43") (pin "1") (pinfunction "1_1") (pintype "passive"))
    )
    (net (code "56") (name "/U1.IN1_p") (class "Default")
      (node (ref "R14") (pin "1") (pinfunction "1_1") (pintype "passive"))
      (node (ref "R15") (pin "2") (pinfunction "2_2") (pintype "passive"))
      (node (ref "R33") (pin "1") (pinfunction "1_1") (pintype "passive"))
    )
    (net (code "57") (name "/U1.IN2_n") (class "Default")
      (node (ref "R55") (pin "1") (pinfunction "1_1") (pintype "passive"))
      (node (ref "R59") (pin "2") (pinfunction "2_2") (pintype "passive"))
      (node (ref "R63") (pin "1") (pinfunction "1_1") (pintype "passive"))
    )
    (net (code "58") (name "/U1.IN2_p") (class "Default")
      (node (ref "R45") (pin "1") (pinfunction "1_1") (pintype "passive"))
      (node (ref "R49") (pin "2") (pinfunction "2_2") (pintype "passive"))
      (node (ref "R53") (pin "1") (pinfunction "1_1") (pintype "passive"))
    )
    (net (code "59") (name "/U1.IN3_n") (class "Default")
      (node (ref "R36") (pin "1") (pinfunction "1_1") (pintype "passive"))
      (node (ref "R42") (pin "2") (pinfunction "2_2") (pintype "passive"))
      (node (ref "R44") (pin "1") (pinfunction "1_1") (pintype "passive"))
    )
    (net (code "60") (name "/U1.IN3_p") (class "Default")
      (node (ref "R16") (pin "1") (pinfunction "1_1") (pintype "passive"))
      (node (ref "R32") (pin "2") (pinfunction "2_2") (pintype "passive"))
      (node (ref "R34") (pin "1") (pinfunction "1_1") (pintype "passive"))
    )
    (net (code "61") (name "/U1.IN4_n") (class "Default")
      (node (ref "R56") (pin "1") (pinfunction "1_1") (pintype "passive"))
      (node (ref "R62") (pin "2") (pinfunction "2_2") (pintype "passive"))
      (node (ref "R64") (pin "1") (pinfunction "1_1") (pintype "passive"))
    )
    (net (code "62") (name "/U1.IN4_p") (class "Default")
      (node (ref "R46") (pin "1") (pinfunction "1_1") (pintype "passive"))
      (node (ref "R52") (pin "2") (pinfunction "2_2") (pintype "passive"))
      (node (ref "R54") (pin "1") (pinfunction "1_1") (pintype "passive"))
    )
    (net (code "63") (name "AGND") (class "Default")
      (node (ref "C13") (pin "2") (pinfunction "2_2") (pintype "passive"))
      (node (ref "C14") (pin "2") (pinfunction "2_2") (pintype "passive"))
      (node (ref "C15") (pin "2") (pinfunction "2_2") (pintype "passive"))
      (node (ref "C16") (pin "2") (pinfunction "2_2") (pintype "passive"))
      (node (ref "C17") (pin "2") (pinfunction "2_2") (pintype "passive"))
      (node (ref "C18") (pin "2") (pinfunction "2_2") (pintype "passive"))
      (node (ref "C19") (pin "2") (pinfunction "2_2") (pintype "passive"))
      (node (ref "C20") (pin "2") (pinfunction "2_2") (pintype "passive"))
      (node (ref "C26") (pin "2") (pinfunction "2_2") (pintype "passive"))
      (node (ref "C27") (pin "2") (pinfunction "2_2") (pintype "passive"))
      (node (ref "C28") (pin "2") (pinfunction "2_2") (pintype "passive"))
      (node (ref "C29") (pin "2") (pinfunction "2_2") (pintype "passive"))
      (node (ref "C30") (pin "2") (pinfunction "2_2") (pintype "passive"))
      (node (ref "C31") (pin "2") (pinfunction "2_2") (pintype "passive"))
      (node (ref "C32") (pin "2") (pinfunction "2_2") (pintype "passive"))
      (node (ref "C33") (pin "2") (pinfunction "2_2") (pintype "passive"))
      (node (ref "C73") (pin "2") (pinfunction "2_2") (pintype "passive"))
      (node (ref "C74") (pin "2") (pinfunction "2_2") (pintype "passive"))
      (node (ref "JP14") (pin "3") (pinfunction "3_3") (pintype "passive"))
      (node (ref "R158") (pin "2") (pinfunction "2_2") (pintype "passive"))
      (node (ref "R159") (pin "2") (pinfunction "2_2") (pintype "passive"))
    )
    (net (code "64") (name "AVDD_2V5") (class "Default")
      (node (ref "D10") (pin "2") (pinfunction "A2_2") (pintype "passive"))
      (node (ref "D11") (pin "2") (pinfunction "A2_2") (pintype "passive"))
      (node (ref "D20") (pin "2") (pinfunction "A2_2") (pintype "passive"))
      (node (ref "D4") (pin "2") (pinfunction "A2_2") (pintype "passive"))
      (node (ref "D5") (pin "2") (pinfunction "A2_2") (pintype "passive"))
      (node (ref "D6") (pin "2") (pinfunction "A2_2") (pintype "passive"))
      (node (ref "D7") (pin "2") (pinfunction "A2_2") (pintype "passive"))
      (node (ref "D8") (pin "2") (pinfunction "A2_2") (pintype "passive"))
      (node (ref "D9") (pin "2") (pinfunction "A2_2") (pintype "passive"))
      (node (ref "R14") (pin "2") (pinfunction "2_2") (pintype "passive"))
      (node (ref "R157") (pin "2") (pinfunction "2_2") (pintype "passive"))
      (node (ref "R16") (pin "2") (pinfunction "2_2") (pintype "passive"))
      (node (ref "R35") (pin "2") (pinfunction "2_2") (pintype "passive"))
      (node (ref "R36") (pin "2") (pinfunction "2_2") (pintype "passive"))
      (node (ref "R45") (pin "2") (pinfunction "2_2") (pintype "passive"))
      (node (ref "R46") (pin "2") (pinfunction "2_2") (pintype "passive"))
      (node (ref "R55") (pin "2") (pinfunction "2_2") (pintype "passive"))
      (node (ref "R56") (pin "2") (pinfunction "2_2") (pintype "passive"))
    )
    (net (code "65") (name "AVSS_2V5n") (class "Default")
      (node (ref "D10") (pin "1") (pinfunction "A1_1") (pintype "passive"))
      (node (ref "D11") (pin "1") (pinfunction "A1_1") (pintype "passive"))
      (node (ref "D20") (pin "1") (pinfunction "A1_1") (pintype "passive"))
      (node (ref "D4") (pin "1") (pinfunction "A1_1") (pintype "passive"))
      (node (ref "D5") (pin "1") (pinfunction "A1_1") (pintype "passive"))
      (node (ref "D6") (pin "1") (pinfunction "A1_1") (pintype "passive"))
      (node (ref "D7") (pin "1") (pinfunction "A1_1") (pintype "passive"))
      (node (ref "D8") (pin "1") (pinfunction "A1_1") (pintype "passive"))
      (node (ref "D9") (pin "1") (pinfunction "A1_1") (pintype "passive"))
      (node (ref "R156") (pin "2") (pinfunction "2_2") (pintype "passive"))
      (node (ref "R33") (pin "2") (pinfunction "2_2") (pintype "passive"))
      (node (ref "R34") (pin "2") (pinfunction "2_2") (pintype "passive"))
      (node (ref "R43") (pin "2") (pinfunction "2_2") (pintype "passive"))
      (node (ref "R44") (pin "2") (pinfunction "2_2") (pintype "passive"))
      (node (ref "R53") (pin "2") (pinfunction "2_2") (pintype "passive"))
      (node (ref "R54") (pin "2") (pinfunction "2_2") (pintype "passive"))
      (node (ref "R63") (pin "2") (pinfunction "2_2") (pintype "passive"))
      (node (ref "R64") (pin "2") (pinfunction "2_2") (pintype "passive"))
    )
    (net (code "66") (name "Net-(J1-Pad37)") (class "Default")
      (node (ref "J1") (pin "37") (pinfunction "37_37") (pintype "passive"))
      (node (ref "R159") (pin "1") (pinfunction "1_1") (pintype "passive"))
    )
    (net (code "67") (name "Net-(J1-Pad38)") (class "Default")
      (node (ref "J1") (pin "38") (pinfunction "38_38") (pintype "passive"))
      (node (ref "R156") (pin "1") (pinfunction "1_1") (pintype "passive"))
    )
    (net (code "68") (name "Net-(J1-Pad39)") (class "Default")
      (node (ref "J1") (pin "39") (pinfunction "39_39") (pintype "passive"))
      (node (ref "R158") (pin "1") (pinfunction "1_1") (pintype "passive"))
    )
    (net (code "69") (name "Net-(J1-Pad40)") (class "Default")
      (node (ref "J1") (pin "40") (pinfunction "40_40") (pintype "passive"))
      (node (ref "R157") (pin "1") (pinfunction "1_1") (pintype "passive"))
    )
    (net (code "70") (name "unconnected-(J1-Pad35)") (class "Default")
      (node (ref "J1") (pin "35") (pinfunction "35_35") (pintype "passive+no_connect"))
    )
    (net (code "71") (name "unconnected-(J1-Pad36)") (class "Default")
      (node (ref "J1") (pin "36") (pinfunction "36_36") (pintype "passive+no_connect"))
    )
  )
)
